# MCU.net
KiCad netlist of a schematic drawn in Altium Designer
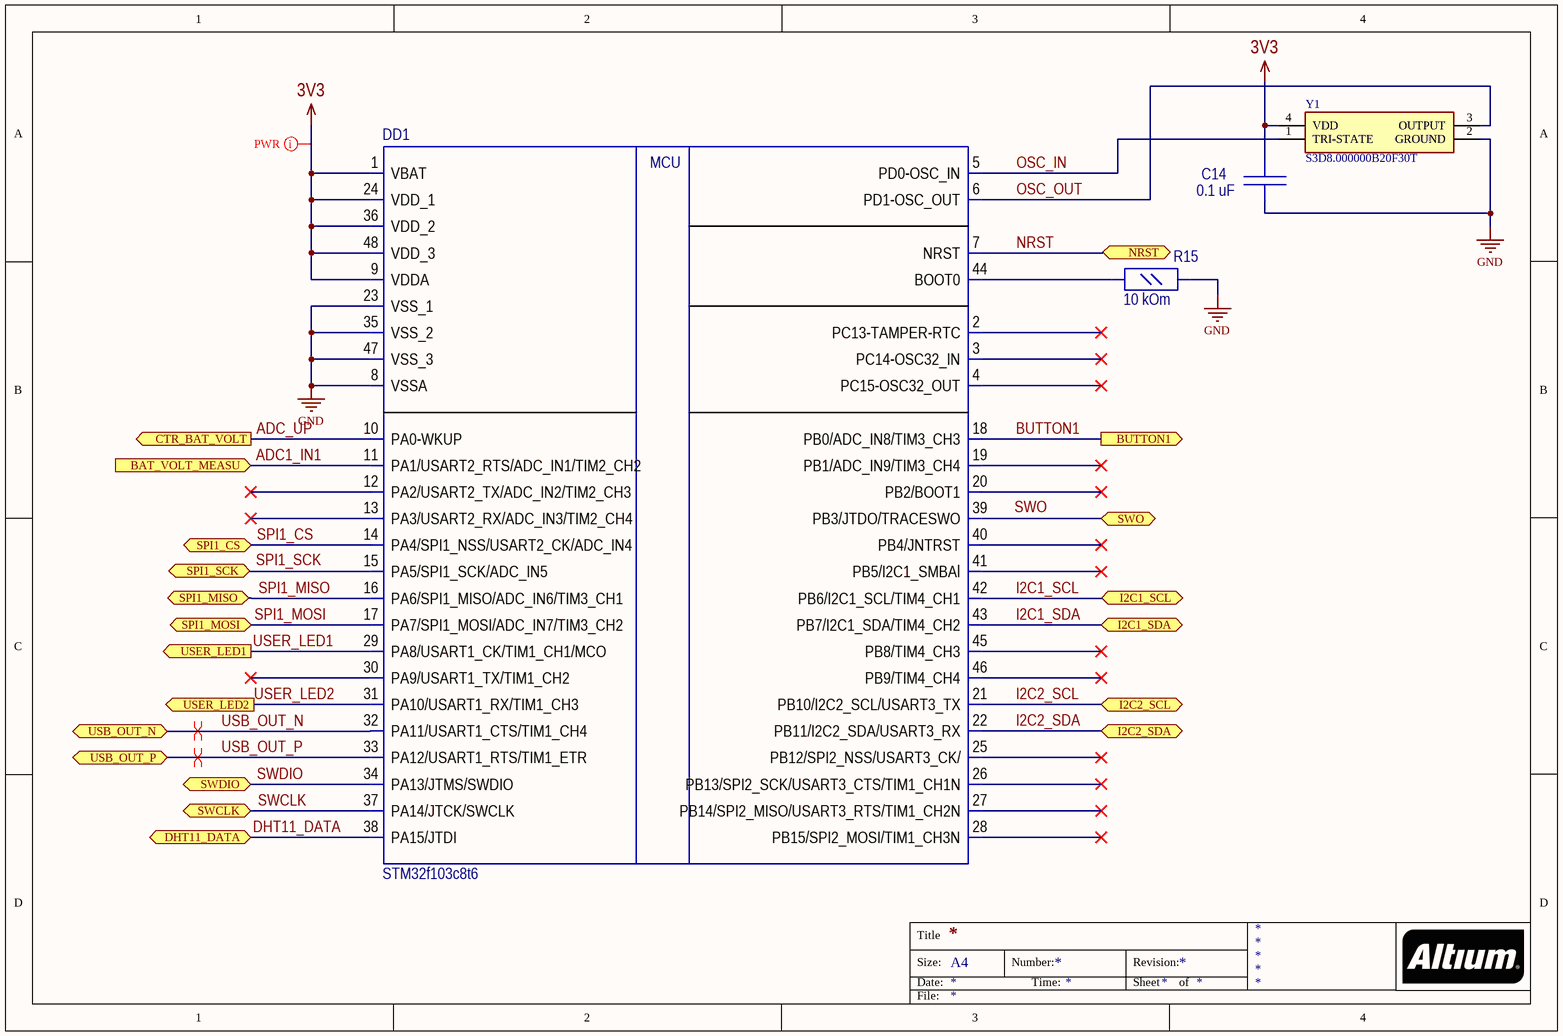
[diagram p0: MCU.SchDoc]

(export (version "E")
  (design (tool "Eeschema 10.0.6"))
  (components
    (comp (ref "C14") (value "0.1 uF") (footprint "C_0805") (libsource (lib "2.Capasitors") (part "C_0805")))
    (comp (ref "DD1")
      (value "STM32f103c8t6")
      (footprint "LQFP48")
      (libsource (lib "6.Chips") (part "STM32f103c8t6"))
    )
    (comp (ref "R15") (value "10 kOm") (footprint "R_0805") (libsource (lib "1.Resistors") (part "R_0805")))
    (comp (ref "Y1")
      (value "S3D8.000000B20F30T")
      (footprint "SamacSys:S3D8000000B20F30T")
      (description "Crystal or Oscillator")
      (libsource (lib "*") (part "S3D8.000000B20F30T"))
    )
  )
  (nets
    (net (code "2") (name "/ADC_UP") (class "Default")
      (node (ref "DD1") (pin "10") (pinfunction "PA0-WKUP_10") (pintype "passive"))
    )
    (net (code "3") (name "/BAT_VOLT_MEASU") (class "Default")
      (node (ref "DD1") (pin "11") (pinfunction "PA1/USART2_RTS/ADC_IN1/TIM2_CH2_11") (pintype "passive"))
    )
    (net (code "4") (name "/BUTTON1") (class "Default")
      (node (ref "DD1") (pin "18") (pinfunction "PB0/ADC_IN8/TIM3_CH3_18") (pintype "passive"))
    )
    (net (code "5") (name "/DHT11_DATA") (class "Default")
      (node (ref "DD1") (pin "38") (pinfunction "PA15/JTDI_38") (pintype "passive"))
    )
    (net (code "6") (name "/I2C1_SCL") (class "Default")
      (node (ref "DD1") (pin "42") (pinfunction "PB6/I2C1_SCL/TIM4_CH1_42") (pintype "passive"))
    )
    (net (code "7") (name "/I2C1_SDA") (class "Default")
      (node (ref "DD1") (pin "43") (pinfunction "PB7/I2C1_SDA/TIM4_CH2_43") (pintype "passive"))
    )
    (net (code "8") (name "/I2C2_SCL") (class "Default")
      (node (ref "DD1") (pin "21") (pinfunction "PB10/I2C2_SCL/USART3_TX_21") (pintype "passive"))
    )
    (net (code "9") (name "/I2C2_SDA") (class "Default")
      (node (ref "DD1") (pin "22") (pinfunction "PB11/I2C2_SDA/USART3_RX_22") (pintype "passive"))
    )
    (net (code "10") (name "/NRST") (class "Default")
      (node (ref "DD1") (pin "7") (pinfunction "NRST_7") (pintype "passive"))
    )
    (net (code "11") (name "/OSC_IN") (class "Default")
      (node (ref "DD1") (pin "5") (pinfunction "PD0-OSC_IN_5") (pintype "passive"))
      (node (ref "Y1") (pin "1") (pinfunction "TRI-STATE_1") (pintype "passive"))
    )
    (net (code "12") (name "/OSC_OUT") (class "Default")
      (node (ref "DD1") (pin "6") (pinfunction "PD1-OSC_OUT_6") (pintype "passive"))
      (node (ref "Y1") (pin "3") (pinfunction "OUTPUT_3") (pintype "passive"))
    )
    (net (code "13") (name "/SPI1_CS") (class "Default")
      (node (ref "DD1") (pin "14") (pinfunction "PA4/SPI1_NSS/USART2_CK/ADC_IN4_14") (pintype "passive"))
    )
    (net (code "14") (name "/SPI1_MISO") (class "Default")
      (node (ref "DD1") (pin "16") (pinfunction "PA6/SPI1_MISO/ADC_IN6/TIM3_CH1_16") (pintype "passive"))
    )
    (net (code "15") (name "/SPI1_MOSI") (class "Default")
      (node (ref "DD1") (pin "17") (pinfunction "PA7/SPI1_MOSI/ADC_IN7/TIM3_CH2_17") (pintype "passive"))
    )
    (net (code "16") (name "/SPI1_SCK") (class "Default")
      (node (ref "DD1") (pin "15") (pinfunction "PA5/SPI1_SCK/ADC_IN5_15") (pintype "passive"))
    )
    (net (code "17") (name "/SWCLK") (class "Default")
      (node (ref "DD1") (pin "37") (pinfunction "PA14/JTCK/SWCLK_37") (pintype "passive"))
    )
    (net (code "18") (name "/SWDIO") (class "Default")
      (node (ref "DD1") (pin "34") (pinfunction "PA13/JTMS/SWDIO_34") (pintype "passive"))
    )
    (net (code "19") (name "/SWO") (class "Default")
      (node (ref "DD1") (pin "39") (pinfunction "PB3/JTDO/TRACESWO_39") (pintype "passive"))
    )
    (net (code "20") (name "/USB_OUT_N") (class "Default")
      (node (ref "DD1") (pin "32") (pinfunction "PA11/USART1_CTS/TIM1_CH4_32") (pintype "passive"))
    )
    (net (code "21") (name "/USB_OUT_P") (class "Default")
      (node (ref "DD1") (pin "33") (pinfunction "PA12/USART1_RTS/TIM1_ETR_33") (pintype "passive"))
    )
    (net (code "22") (name "/USER_LED1") (class "Default")
      (node (ref "DD1") (pin "29") (pinfunction "PA8/USART1_CK/TIM1_CH1/MCO_29") (pintype "passive"))
    )
    (net (code "23") (name "/USER_LED2") (class "Default")
      (node (ref "DD1") (pin "31") (pinfunction "PA10/USART1_RX/TIM1_CH3_31") (pintype "passive"))
    )
    (net (code "24") (name "3V3") (class "Default")
      (node (ref "C14") (pin "2") (pinfunction "2_2") (pintype "passive"))
      (node (ref "DD1") (pin "1") (pinfunction "VBAT_1") (pintype "passive"))
      (node (ref "DD1") (pin "24") (pinfunction "VDD_1_24") (pintype "passive"))
      (node (ref "DD1") (pin "36") (pinfunction "VDD_2_36") (pintype "passive"))
      (node (ref "DD1") (pin "48") (pinfunction "VDD_3_48") (pintype "passive"))
      (node (ref "DD1") (pin "9") (pinfunction "VDDA_9") (pintype "passive"))
      (node (ref "Y1") (pin "4") (pinfunction "VDD_4") (pintype "passive"))
    )
    (net (code "25") (name "GND") (class "Default")
      (node (ref "C14") (pin "1") (pinfunction "1_1") (pintype "passive"))
      (node (ref "DD1") (pin "23") (pinfunction "VSS_1_23") (pintype "passive"))
      (node (ref "DD1") (pin "35") (pinfunction "VSS_2_35") (pintype "passive"))
      (node (ref "DD1") (pin "47") (pinfunction "VSS_3_47") (pintype "passive"))
      (node (ref "DD1") (pin "8") (pinfunction "VSSA_8") (pintype "passive"))
      (node (ref "R15") (pin "1") (pinfunction "1_1") (pintype "passive"))
      (node (ref "Y1") (pin "2") (pinfunction "GROUND_2") (pintype "passive"))
    )
    (net (code "26") (name "Net-(DD1-BOOT0)") (class "Default")
      (node (ref "DD1") (pin "44") (pinfunction "BOOT0_44") (pintype "passive"))
      (node (ref "R15") (pin "2") (pinfunction "2_2") (pintype "passive"))
    )
    (net (code "27") (name "unconnected-(DD1-PA2{slash}USART2_TX{slash}ADC_IN2{slash}TIM2_CH3-Pad12)") (class "Default")
      (node (ref "DD1") (pin "12") (pinfunction "PA2/USART2_TX/ADC_IN2/TIM2_CH3_12") (pintype "passive+no_connect"))
    )
    (net (code "28") (name "unconnected-(DD1-PA3{slash}USART2_RX{slash}ADC_IN3{slash}TIM2_CH4-Pad13)") (class "Default")
      (node (ref "DD1") (pin "13") (pinfunction "PA3/USART2_RX/ADC_IN3/TIM2_CH4_13") (pintype "passive+no_connect"))
    )
    (net (code "29") (name "unconnected-(DD1-PA9{slash}USART1_TX{slash}TIM1_CH2-Pad30)") (class "Default")
      (node (ref "DD1") (pin "30") (pinfunction "PA9/USART1_TX/TIM1_CH2_30") (pintype "passive+no_connect"))
    )
    (net (code "30") (name "unconnected-(DD1-PB1{slash}ADC_IN9{slash}TIM3_CH4-Pad19)") (class "Default")
      (node (ref "DD1") (pin "19") (pinfunction "PB1/ADC_IN9/TIM3_CH4_19") (pintype "passive+no_connect"))
    )
    (net (code "31") (name "unconnected-(DD1-PB2{slash}BOOT1-Pad20)") (class "Default")
      (node (ref "DD1") (pin "20") (pinfunction "PB2/BOOT1_20") (pintype "passive+no_connect"))
    )
    (net (code "32") (name "unconnected-(DD1-PB4{slash}JNTRST-Pad40)") (class "Default")
      (node (ref "DD1") (pin "40") (pinfunction "PB4/JNTRST_40") (pintype "passive+no_connect"))
    )
    (net (code "33") (name "unconnected-(DD1-PB5{slash}I2C1_SMBAl-Pad41)") (class "Default")
      (node (ref "DD1") (pin "41") (pinfunction "PB5/I2C1_SMBAl_41") (pintype "passive+no_connect"))
    )
    (net (code "34") (name "unconnected-(DD1-PB8{slash}TIM4_CH3-Pad45)") (class "Default")
      (node (ref "DD1") (pin "45") (pinfunction "PB8/TIM4_CH3_45") (pintype "passive+no_connect"))
    )
    (net (code "35") (name "unconnected-(DD1-PB9{slash}TIM4_CH4-Pad46)") (class "Default")
      (node (ref "DD1") (pin "46") (pinfunction "PB9/TIM4_CH4_46") (pintype "passive+no_connect"))
    )
    (net (code "36") (name "unconnected-(DD1-PB12{slash}SPI2_NSS{slash}USART3_CK{slash}-Pad25)") (class "Default")
      (node (ref "DD1") (pin "25") (pinfunction "PB12/SPI2_NSS/USART3_CK/_25") (pintype "passive+no_connect"))
    )
    (net (code "37") (name "unconnected-(DD1-PB13{slash}SPI2_SCK{slash}USART3_CTS{slash}TIM1_CH1N-Pad26)") (class "Default")
      (node (ref "DD1") (pin "26") (pinfunction "PB13/SPI2_SCK/USART3_CTS/TIM1_CH1N_26") (pintype "passive+no_connect"))
    )
    (net (code "38") (name "unconnected-(DD1-PB14{slash}SPI2_MISO{slash}USART3_RTS{slash}TIM1_CH2N-Pad27)") (class "Default")
      (node (ref "DD1") (pin "27") (pinfunction "PB14/SPI2_MISO/USART3_RTS/TIM1_CH2N_27") (pintype "passive+no_connect"))
    )
    (net (code "39") (name "unconnected-(DD1-PB15{slash}SPI2_MOSI{slash}TIM1_CH3N-Pad28)") (class "Default")
      (node (ref "DD1") (pin "28") (pinfunction "PB15/SPI2_MOSI/TIM1_CH3N_28") (pintype "passive+no_connect"))
    )
    (net (code "40") (name "unconnected-(DD1-PC13-TAMPER-RTC-Pad2)") (class "Default")
      (node (ref "DD1") (pin "2") (pinfunction "PC13-TAMPER-RTC_2") (pintype "passive+no_connect"))
    )
    (net (code "41") (name "unconnected-(DD1-PC14-OSC32_IN-Pad3)") (class "Default")
      (node (ref "DD1") (pin "3") (pinfunction "PC14-OSC32_IN_3") (pintype "passive+no_connect"))
    )
    (net (code "42") (name "unconnected-(DD1-PC15-OSC32_OUT-Pad4)") (class "Default")
      (node (ref "DD1") (pin "4") (pinfunction "PC15-OSC32_OUT_4") (pintype "passive+no_connect"))
    )
  )
)
